# midiprog.net
KiCad netlist of a schematic drawn in EAGLE
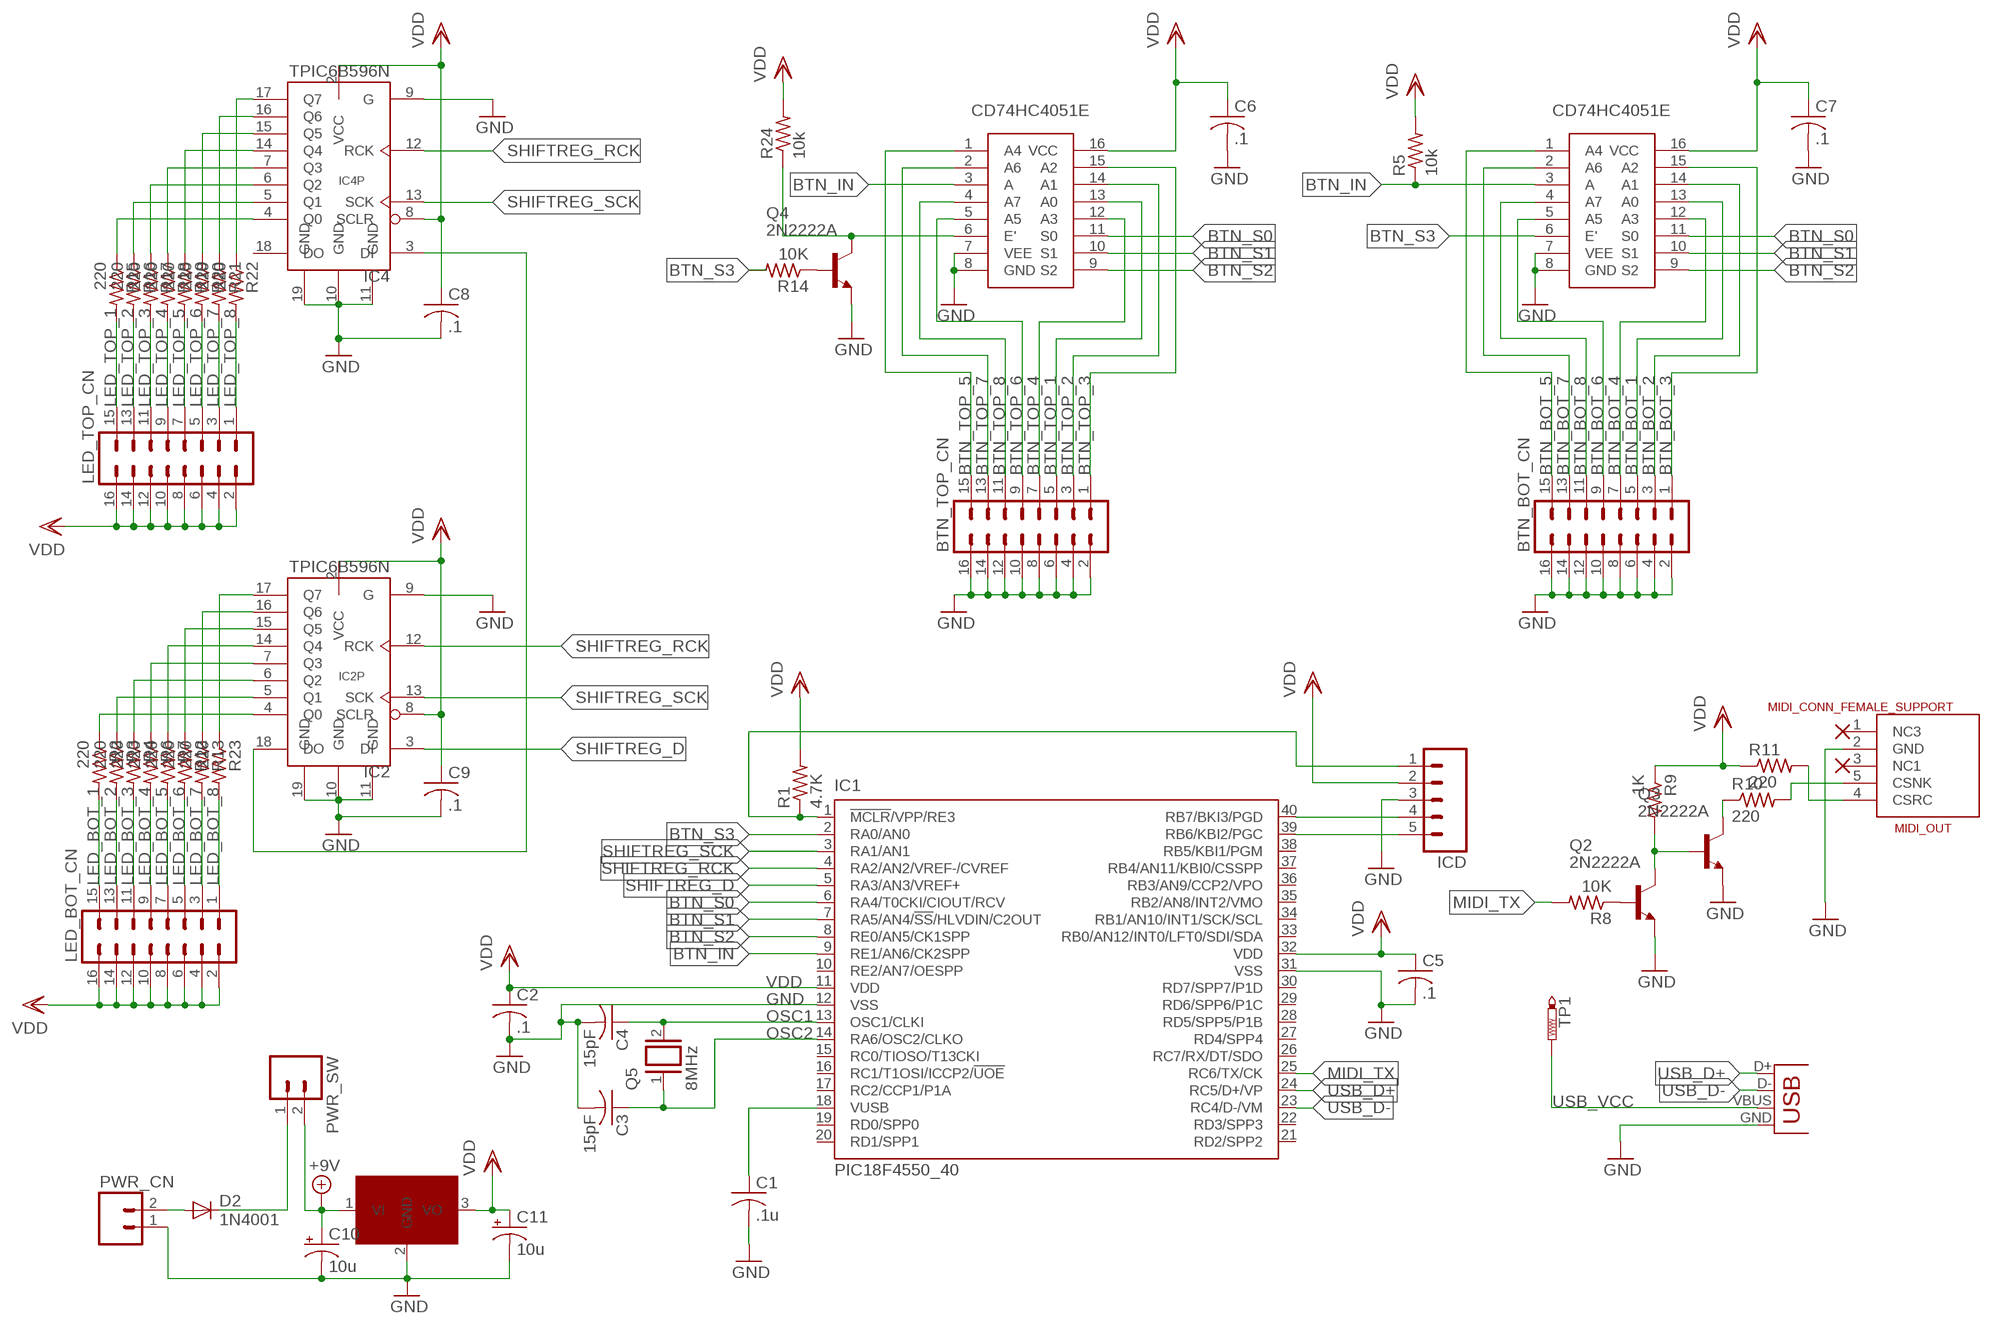
[diagram p0: schematic, sheet 1]

(export (version "E")
  (design (tool "Eeschema 10.0.6"))
  (components
    (comp (ref "BTN_BOT_CN")
      (value "MA08-2")
      (footprint "eagle-import:MA08-2")
      (libsource (lib "eagle-import") (part "MA08-2"))
    )
    (comp (ref "BTN_TOP_CN")
      (value "MA08-2")
      (footprint "eagle-import:MA08-2")
      (libsource (lib "eagle-import") (part "MA08-2"))
    )
    (comp (ref "C1")
      (value ".1u")
      (footprint "eagle-import:C050-025X075")
      (libsource (lib "eagle-import") (part "C-US050-025X075"))
    )
    (comp (ref "C2")
      (value ".1")
      (footprint "eagle-import:C050-025X075")
      (libsource (lib "eagle-import") (part "C-US050-025X075"))
    )
    (comp (ref "C3")
      (value "15pF")
      (footprint "eagle-import:C050-025X075")
      (libsource (lib "eagle-import") (part "C-US050-025X075"))
    )
    (comp (ref "C4")
      (value "15pF")
      (footprint "eagle-import:C050-025X075")
      (libsource (lib "eagle-import") (part "C-US050-025X075"))
    )
    (comp (ref "C5")
      (value ".1")
      (footprint "eagle-import:C050-025X075")
      (libsource (lib "eagle-import") (part "C-US050-025X075"))
    )
    (comp (ref "C6")
      (value ".1")
      (footprint "eagle-import:C050-025X075")
      (libsource (lib "eagle-import") (part "C-US050-025X075"))
    )
    (comp (ref "C7")
      (value ".1")
      (footprint "eagle-import:C050-025X075")
      (libsource (lib "eagle-import") (part "C-US050-025X075"))
    )
    (comp (ref "C8")
      (value ".1")
      (footprint "eagle-import:C050-025X075")
      (libsource (lib "eagle-import") (part "C-US050-025X075"))
    )
    (comp (ref "C9")
      (value ".1")
      (footprint "eagle-import:C050-025X075")
      (libsource (lib "eagle-import") (part "C-US050-025X075"))
    )
    (comp (ref "C10")
      (value "10u")
      (footprint "eagle-import:E2,5-6")
      (libsource (lib "eagle-import") (part "CPOL-USE2.5-6"))
    )
    (comp (ref "C11")
      (value "10u")
      (footprint "eagle-import:E2,5-6")
      (libsource (lib "eagle-import") (part "CPOL-USE2.5-6"))
    )
    (comp (ref "D2")
      (value "1N4001")
      (footprint "eagle-import:DO41-10")
      (libsource (lib "eagle-import") (part "1N4004"))
    )
    (comp (ref "IC1")
      (value "PIC18F4550_40")
      (footprint "eagle-import:DIL40")
      (fields (field (name "MF") "MICROCHIP") (field (name "MPN") "PIC18F4550-I/P"))
      (libsource (lib "eagle-import") (part "PIC18F4_40550"))
    )
    (comp (ref "IC2")
      (value "TPIC6B596N")
      (footprint "eagle-import:DIL20")
      (libsource (lib "eagle-import") (part "TPIC6B596N"))
    )
    (comp (ref "IC4")
      (value "TPIC6B596N")
      (footprint "eagle-import:DIL20")
      (libsource (lib "eagle-import") (part "TPIC6B596N"))
    )
    (comp (ref "ICD")
      (value "MA05")
      (footprint "eagle-import:05PA")
      (libsource (lib "eagle-import") (part "MA05"))
    )
    (comp (ref "JP1")
      (value "USB-B")
      (footprint "eagle-import:USB-B-PTH")
      (libsource (lib "eagle-import") (part "USBPTH"))
    )
    (comp (ref "LED_BOT_CN")
      (value "MA08-2")
      (footprint "eagle-import:MA08-2")
      (libsource (lib "eagle-import") (part "MA08-2"))
    )
    (comp (ref "LED_TOP_CN")
      (value "MA08-2")
      (footprint "eagle-import:MA08-2")
      (libsource (lib "eagle-import") (part "MA08-2"))
    )
    (comp (ref "MIDI_OUT")
      (value "MIDI_CONN_FEMALE_SUPPORT")
      (footprint "eagle-import:DIN_5_FEMALE_SUPPORT")
      (libsource (lib "eagle-import") (part "MIDI_CONN_FEMALE_SUPPORT"))
    )
    (comp (ref "PWR_CN")
      (value "M02")
      (footprint "eagle-import:02P")
      (libsource (lib "eagle-import") (part "M02"))
    )
    (comp (ref "PWR_SW")
      (value "M02")
      (footprint "eagle-import:02P")
      (libsource (lib "eagle-import") (part "M02"))
    )
    (comp (ref "Q2")
      (value "2N2222A")
      (footprint "eagle-import:TO18")
      (libsource (lib "eagle-import") (part "2N2222A"))
    )
    (comp (ref "Q3")
      (value "2N2222A")
      (footprint "eagle-import:TO18")
      (libsource (lib "eagle-import") (part "2N2222A"))
    )
    (comp (ref "Q4")
      (value "2N2222A")
      (footprint "eagle-import:TO18")
      (libsource (lib "eagle-import") (part "2N2222A"))
    )
    (comp (ref "Q5")
      (value "8MHz")
      (footprint "eagle-import:QS")
      (libsource (lib "eagle-import") (part "XTAL/S"))
    )
    (comp (ref "R1")
      (value "4.7K")
      (footprint "eagle-import:0207_10")
      (libsource (lib "eagle-import") (part "R-US_0207/10"))
    )
    (comp (ref "R2")
      (value "220")
      (footprint "eagle-import:0207_10")
      (libsource (lib "eagle-import") (part "R-US_0207/10"))
    )
    (comp (ref "R3")
      (value "220")
      (footprint "eagle-import:0207_10")
      (libsource (lib "eagle-import") (part "R-US_0207/10"))
    )
    (comp (ref "R4")
      (value "220")
      (footprint "eagle-import:0207_10")
      (libsource (lib "eagle-import") (part "R-US_0207/10"))
    )
    (comp (ref "R5")
      (value "10k")
      (footprint "eagle-import:0207_10")
      (libsource (lib "eagle-import") (part "R-US_0207/10"))
    )
    (comp (ref "R6")
      (value "220")
      (footprint "eagle-import:0207_10")
      (libsource (lib "eagle-import") (part "R-US_0207/10"))
    )
    (comp (ref "R7")
      (value "220")
      (footprint "eagle-import:0207_10")
      (libsource (lib "eagle-import") (part "R-US_0207/10"))
    )
    (comp (ref "R8")
      (value "10K")
      (footprint "eagle-import:0207_10")
      (libsource (lib "eagle-import") (part "R-US_0207/10"))
    )
    (comp (ref "R9")
      (value "1K")
      (footprint "eagle-import:0207_10")
      (libsource (lib "eagle-import") (part "R-US_0207/10"))
    )
    (comp (ref "R10")
      (value "220")
      (footprint "eagle-import:0207_10")
      (libsource (lib "eagle-import") (part "R-US_0207/10"))
    )
    (comp (ref "R11")
      (value "220")
      (footprint "eagle-import:0207_10")
      (libsource (lib "eagle-import") (part "R-US_0207/10"))
    )
    (comp (ref "R12")
      (value "220")
      (footprint "eagle-import:0207_10")
      (libsource (lib "eagle-import") (part "R-US_0207/10"))
    )
    (comp (ref "R13")
      (value "220")
      (footprint "eagle-import:0207_10")
      (libsource (lib "eagle-import") (part "R-US_0207/10"))
    )
    (comp (ref "R14")
      (value "10K")
      (footprint "eagle-import:0207_10")
      (libsource (lib "eagle-import") (part "R-US_0207/10"))
    )
    (comp (ref "R15")
      (value "220")
      (footprint "eagle-import:0207_10")
      (libsource (lib "eagle-import") (part "R-US_0207/10"))
    )
    (comp (ref "R16")
      (value "220")
      (footprint "eagle-import:0207_10")
      (libsource (lib "eagle-import") (part "R-US_0207/10"))
    )
    (comp (ref "R17")
      (value "220")
      (footprint "eagle-import:0207_10")
      (libsource (lib "eagle-import") (part "R-US_0207/10"))
    )
    (comp (ref "R18")
      (value "220")
      (footprint "eagle-import:0207_10")
      (libsource (lib "eagle-import") (part "R-US_0207/10"))
    )
    (comp (ref "R19")
      (value "220")
      (footprint "eagle-import:0207_10")
      (libsource (lib "eagle-import") (part "R-US_0207/10"))
    )
    (comp (ref "R20")
      (value "220")
      (footprint "eagle-import:0207_10")
      (libsource (lib "eagle-import") (part "R-US_0207/10"))
    )
    (comp (ref "R21")
      (value "220")
      (footprint "eagle-import:0207_10")
      (libsource (lib "eagle-import") (part "R-US_0207/10"))
    )
    (comp (ref "R22")
      (value "220")
      (footprint "eagle-import:0207_10")
      (libsource (lib "eagle-import") (part "R-US_0207/10"))
    )
    (comp (ref "R23")
      (value "220")
      (footprint "eagle-import:0207_10")
      (libsource (lib "eagle-import") (part "R-US_0207/10"))
    )
    (comp (ref "R24")
      (value "10k")
      (footprint "eagle-import:0207_10")
      (libsource (lib "eagle-import") (part "R-US_0207/10"))
    )
    (comp (ref "TP1")
      (value "PTR1PAD1-17")
      (footprint "eagle-import:P1-17")
      (libsource (lib "eagle-import") (part "PTR1PAD1-17"))
    )
    (comp (ref "U$1")
      (value "CD74HC4051E")
      (footprint "eagle-import:CD74HC4051E")
      (libsource (lib "eagle-import") (part "CD74HC4051E"))
    )
    (comp (ref "U$2")
      (value "CD74HC4051E")
      (footprint "eagle-import:CD74HC4051E")
      (libsource (lib "eagle-import") (part "CD74HC4051E"))
    )
    (comp (ref "U$3")
      (value "7805")
      (footprint "eagle-import:JKDFJD")
      (libsource (lib "eagle-import") (part "7805"))
    )
  )
  (nets
    (net (code "1") (name "+9V") (class "Default")
      (node (ref "C10") (pin "+") (pinfunction "+_+") (pintype "passive"))
      (node (ref "PWR_SW") (pin "2") (pinfunction "2_2") (pintype "passive"))
      (node (ref "U$3") (pin "1") (pinfunction "VI_1") (pintype "bidirectional"))
    )
    (net (code "2") (name "/BTN_BOT_1") (class "Default")
      (node (ref "BTN_BOT_CN") (pin "5") (pinfunction "5_5") (pintype "passive"))
      (node (ref "U$1") (pin "13") (pinfunction "A0_13") (pintype "bidirectional"))
    )
    (net (code "3") (name "/BTN_BOT_2") (class "Default")
      (node (ref "BTN_BOT_CN") (pin "3") (pinfunction "3_3") (pintype "passive"))
      (node (ref "U$1") (pin "14") (pinfunction "A1_14") (pintype "bidirectional"))
    )
    (net (code "4") (name "/BTN_BOT_3") (class "Default")
      (node (ref "BTN_BOT_CN") (pin "1") (pinfunction "1_1") (pintype "passive"))
      (node (ref "U$1") (pin "15") (pinfunction "A2_15") (pintype "bidirectional"))
    )
    (net (code "5") (name "/BTN_BOT_4") (class "Default")
      (node (ref "BTN_BOT_CN") (pin "7") (pinfunction "7_7") (pintype "passive"))
      (node (ref "U$1") (pin "12") (pinfunction "A3_12") (pintype "bidirectional"))
    )
    (net (code "6") (name "/BTN_BOT_5") (class "Default")
      (node (ref "BTN_BOT_CN") (pin "15") (pinfunction "15_15") (pintype "passive"))
      (node (ref "U$1") (pin "1") (pinfunction "A4_1") (pintype "bidirectional"))
    )
    (net (code "7") (name "/BTN_BOT_6") (class "Default")
      (node (ref "BTN_BOT_CN") (pin "9") (pinfunction "9_9") (pintype "passive"))
      (node (ref "U$1") (pin "5") (pinfunction "A5_5") (pintype "bidirectional"))
    )
    (net (code "8") (name "/BTN_BOT_7") (class "Default")
      (node (ref "BTN_BOT_CN") (pin "13") (pinfunction "13_13") (pintype "passive"))
      (node (ref "U$1") (pin "2") (pinfunction "A6_2") (pintype "bidirectional"))
    )
    (net (code "9") (name "/BTN_BOT_8") (class "Default")
      (node (ref "BTN_BOT_CN") (pin "11") (pinfunction "11_11") (pintype "passive"))
      (node (ref "U$1") (pin "4") (pinfunction "A7_4") (pintype "bidirectional"))
    )
    (net (code "10") (name "/BTN_TOP_1") (class "Default")
      (node (ref "BTN_TOP_CN") (pin "5") (pinfunction "5_5") (pintype "passive"))
      (node (ref "U$2") (pin "13") (pinfunction "A0_13") (pintype "bidirectional"))
    )
    (net (code "11") (name "/BTN_TOP_2") (class "Default")
      (node (ref "BTN_TOP_CN") (pin "3") (pinfunction "3_3") (pintype "passive"))
      (node (ref "U$2") (pin "14") (pinfunction "A1_14") (pintype "bidirectional"))
    )
    (net (code "12") (name "/BTN_TOP_3") (class "Default")
      (node (ref "BTN_TOP_CN") (pin "1") (pinfunction "1_1") (pintype "passive"))
      (node (ref "U$2") (pin "15") (pinfunction "A2_15") (pintype "bidirectional"))
    )
    (net (code "13") (name "/BTN_TOP_4") (class "Default")
      (node (ref "BTN_TOP_CN") (pin "7") (pinfunction "7_7") (pintype "passive"))
      (node (ref "U$2") (pin "12") (pinfunction "A3_12") (pintype "bidirectional"))
    )
    (net (code "14") (name "/BTN_TOP_5") (class "Default")
      (node (ref "BTN_TOP_CN") (pin "15") (pinfunction "15_15") (pintype "passive"))
      (node (ref "U$2") (pin "1") (pinfunction "A4_1") (pintype "bidirectional"))
    )
    (net (code "15") (name "/BTN_TOP_6") (class "Default")
      (node (ref "BTN_TOP_CN") (pin "9") (pinfunction "9_9") (pintype "passive"))
      (node (ref "U$2") (pin "5") (pinfunction "A5_5") (pintype "bidirectional"))
    )
    (net (code "16") (name "/BTN_TOP_7") (class "Default")
      (node (ref "BTN_TOP_CN") (pin "13") (pinfunction "13_13") (pintype "passive"))
      (node (ref "U$2") (pin "2") (pinfunction "A6_2") (pintype "bidirectional"))
    )
    (net (code "17") (name "/BTN_TOP_8") (class "Default")
      (node (ref "BTN_TOP_CN") (pin "11") (pinfunction "11_11") (pintype "passive"))
      (node (ref "U$2") (pin "4") (pinfunction "A7_4") (pintype "bidirectional"))
    )
    (net (code "18") (name "/LED_BOT_1") (class "Default")
      (node (ref "LED_BOT_CN") (pin "15") (pinfunction "15_15") (pintype "passive"))
      (node (ref "R2") (pin "2") (pinfunction "2_2") (pintype "passive"))
    )
    (net (code "19") (name "/LED_BOT_2") (class "Default")
      (node (ref "LED_BOT_CN") (pin "13") (pinfunction "13_13") (pintype "passive"))
      (node (ref "R3") (pin "2") (pinfunction "2_2") (pintype "passive"))
    )
    (net (code "20") (name "/LED_BOT_3") (class "Default")
      (node (ref "LED_BOT_CN") (pin "11") (pinfunction "11_11") (pintype "passive"))
      (node (ref "R4") (pin "2") (pinfunction "2_2") (pintype "passive"))
    )
    (net (code "21") (name "/LED_BOT_4") (class "Default")
      (node (ref "LED_BOT_CN") (pin "9") (pinfunction "9_9") (pintype "passive"))
      (node (ref "R6") (pin "2") (pinfunction "2_2") (pintype "passive"))
    )
    (net (code "22") (name "/LED_BOT_5") (class "Default")
      (node (ref "LED_BOT_CN") (pin "7") (pinfunction "7_7") (pintype "passive"))
      (node (ref "R7") (pin "2") (pinfunction "2_2") (pintype "passive"))
    )
    (net (code "23") (name "/LED_BOT_6") (class "Default")
      (node (ref "LED_BOT_CN") (pin "5") (pinfunction "5_5") (pintype "passive"))
      (node (ref "R12") (pin "2") (pinfunction "2_2") (pintype "passive"))
    )
    (net (code "24") (name "/LED_BOT_7") (class "Default")
      (node (ref "LED_BOT_CN") (pin "3") (pinfunction "3_3") (pintype "passive"))
      (node (ref "R13") (pin "2") (pinfunction "2_2") (pintype "passive"))
    )
    (net (code "25") (name "/LED_BOT_8") (class "Default")
      (node (ref "LED_BOT_CN") (pin "1") (pinfunction "1_1") (pintype "passive"))
      (node (ref "R23") (pin "2") (pinfunction "2_2") (pintype "passive"))
    )
    (net (code "26") (name "/LED_TOP_1") (class "Default")
      (node (ref "LED_TOP_CN") (pin "15") (pinfunction "15_15") (pintype "passive"))
      (node (ref "R15") (pin "2") (pinfunction "2_2") (pintype "passive"))
    )
    (net (code "27") (name "/LED_TOP_2") (class "Default")
      (node (ref "LED_TOP_CN") (pin "13") (pinfunction "13_13") (pintype "passive"))
      (node (ref "R16") (pin "2") (pinfunction "2_2") (pintype "passive"))
    )
    (net (code "28") (name "/LED_TOP_3") (class "Default")
      (node (ref "LED_TOP_CN") (pin "11") (pinfunction "11_11") (pintype "passive"))
      (node (ref "R17") (pin "2") (pinfunction "2_2") (pintype "passive"))
    )
    (net (code "29") (name "/LED_TOP_4") (class "Default")
      (node (ref "LED_TOP_CN") (pin "9") (pinfunction "9_9") (pintype "passive"))
      (node (ref "R18") (pin "2") (pinfunction "2_2") (pintype "passive"))
    )
    (net (code "30") (name "/LED_TOP_5") (class "Default")
      (node (ref "LED_TOP_CN") (pin "7") (pinfunction "7_7") (pintype "passive"))
      (node (ref "R19") (pin "2") (pinfunction "2_2") (pintype "passive"))
    )
    (net (code "31") (name "/LED_TOP_6") (class "Default")
      (node (ref "LED_TOP_CN") (pin "5") (pinfunction "5_5") (pintype "passive"))
      (node (ref "R20") (pin "2") (pinfunction "2_2") (pintype "passive"))
    )
    (net (code "32") (name "/LED_TOP_7") (class "Default")
      (node (ref "LED_TOP_CN") (pin "3") (pinfunction "3_3") (pintype "passive"))
      (node (ref "R21") (pin "2") (pinfunction "2_2") (pintype "passive"))
    )
    (net (code "33") (name "/LED_TOP_8") (class "Default")
      (node (ref "LED_TOP_CN") (pin "1") (pinfunction "1_1") (pintype "passive"))
      (node (ref "R22") (pin "2") (pinfunction "2_2") (pintype "passive"))
    )
    (net (code "34") (name "/OSC1") (class "Default")
      (node (ref "C4") (pin "1") (pinfunction "1_1") (pintype "passive"))
      (node (ref "IC1") (pin "13") (pinfunction "OSC1/CLKI_13") (pintype "input"))
      (node (ref "Q5") (pin "2") (pinfunction "2_2") (pintype "passive"))
    )
    (net (code "35") (name "/OSC2") (class "Default")
      (node (ref "C3") (pin "1") (pinfunction "1_1") (pintype "passive"))
      (node (ref "IC1") (pin "14") (pinfunction "RA6/OSC2/CLKO_14") (pintype "output"))
      (node (ref "Q5") (pin "1") (pinfunction "1_1") (pintype "passive"))
    )
    (net (code "36") (name "/USB_VCC") (class "Default")
      (node (ref "JP1") (pin "VBUS") (pinfunction "VBUS_VBUS") (pintype "bidirectional"))
      (node (ref "TP1") (pin "TP") (pinfunction "TP_TP") (pintype "input"))
    )
    (net (code "37") (name "BTN_IN") (class "Default")
      (node (ref "IC1") (pin "9") (pinfunction "RE1/AN6/CK2SPP_9") (pintype "bidirectional"))
      (node (ref "R5") (pin "1") (pinfunction "1_1") (pintype "passive"))
      (node (ref "U$1") (pin "3") (pinfunction "A_3") (pintype "bidirectional"))
      (node (ref "U$2") (pin "3") (pinfunction "A_3") (pintype "bidirectional"))
    )
    (net (code "38") (name "BTN_S0") (class "Default")
      (node (ref "IC1") (pin "6") (pinfunction "RA4/T0CKI/CIOUT/RCV_6") (pintype "bidirectional"))
      (node (ref "U$1") (pin "11") (pinfunction "S0_11") (pintype "bidirectional"))
      (node (ref "U$2") (pin "11") (pinfunction "S0_11") (pintype "bidirectional"))
    )
    (net (code "39") (name "BTN_S1") (class "Default")
      (node (ref "IC1") (pin "7") (pinfunction "RA5/AN4/~{SS}/HLVDIN/C2OUT_7") (pintype "bidirectional"))
      (node (ref "U$1") (pin "10") (pinfunction "S1_10") (pintype "bidirectional"))
      (node (ref "U$2") (pin "10") (pinfunction "S1_10") (pintype "bidirectional"))
    )
    (net (code "40") (name "BTN_S2") (class "Default")
      (node (ref "IC1") (pin "8") (pinfunction "RE0/AN5/CK1SPP_8") (pintype "bidirectional"))
      (node (ref "U$1") (pin "9") (pinfunction "S2_9") (pintype "bidirectional"))
      (node (ref "U$2") (pin "9") (pinfunction "S2_9") (pintype "bidirectional"))
    )
    (net (code "41") (name "BTN_S3") (class "Default")
      (node (ref "IC1") (pin "2") (pinfunction "RA0/AN0_2") (pintype "bidirectional"))
      (node (ref "R14") (pin "2") (pinfunction "2_2") (pintype "passive"))
      (node (ref "U$1") (pin "6") (pinfunction "E'_6") (pintype "bidirectional"))
    )
    (net (code "42") (name "GND") (class "Default")
      (node (ref "BTN_BOT_CN") (pin "10") (pinfunction "10_10") (pintype "passive"))
      (node (ref "BTN_BOT_CN") (pin "12") (pinfunction "12_12") (pintype "passive"))
      (node (ref "BTN_BOT_CN") (pin "14") (pinfunction "14_14") (pintype "passive"))
      (node (ref "BTN_BOT_CN") (pin "16") (pinfunction "16_16") (pintype "passive"))
      (node (ref "BTN_BOT_CN") (pin "2") (pinfunction "2_2") (pintype "passive"))
      (node (ref "BTN_BOT_CN") (pin "4") (pinfunction "4_4") (pintype "passive"))
      (node (ref "BTN_BOT_CN") (pin "6") (pinfunction "6_6") (pintype "passive"))
      (node (ref "BTN_BOT_CN") (pin "8") (pinfunction "8_8") (pintype "passive"))
      (node (ref "BTN_TOP_CN") (pin "10") (pinfunction "10_10") (pintype "passive"))
      (node (ref "BTN_TOP_CN") (pin "12") (pinfunction "12_12") (pintype "passive"))
      (node (ref "BTN_TOP_CN") (pin "14") (pinfunction "14_14") (pintype "passive"))
      (node (ref "BTN_TOP_CN") (pin "16") (pinfunction "16_16") (pintype "passive"))
      (node (ref "BTN_TOP_CN") (pin "2") (pinfunction "2_2") (pintype "passive"))
      (node (ref "BTN_TOP_CN") (pin "4") (pinfunction "4_4") (pintype "passive"))
      (node (ref "BTN_TOP_CN") (pin "6") (pinfunction "6_6") (pintype "passive"))
      (node (ref "BTN_TOP_CN") (pin "8") (pinfunction "8_8") (pintype "passive"))
      (node (ref "C1") (pin "2") (pinfunction "2_2") (pintype "passive"))
      (node (ref "C10") (pin "-") (pinfunction "-_-") (pintype "passive"))
      (node (ref "C11") (pin "-") (pinfunction "-_-") (pintype "passive"))
      (node (ref "C2") (pin "2") (pinfunction "2_2") (pintype "passive"))
      (node (ref "C3") (pin "2") (pinfunction "2_2") (pintype "passive"))
      (node (ref "C4") (pin "2") (pinfunction "2_2") (pintype "passive"))
      (node (ref "C5") (pin "2") (pinfunction "2_2") (pintype "passive"))
      (node (ref "C6") (pin "2") (pinfunction "2_2") (pintype "passive"))
      (node (ref "C7") (pin "2") (pinfunction "2_2") (pintype "passive"))
      (node (ref "C8") (pin "2") (pinfunction "2_2") (pintype "passive"))
      (node (ref "C9") (pin "2") (pinfunction "2_2") (pintype "passive"))
      (node (ref "IC1") (pin "12") (pinfunction "VSS_12") (pintype "power_in"))
      (node (ref "IC1") (pin "31") (pinfunction "VSS_31") (pintype "power_in"))
      (node (ref "IC2") (pin "10") (pinfunction "GND_10") (pintype "power_in"))
      (node (ref "IC2") (pin "11") (pinfunction "GND_11") (pintype "power_in"))
      (node (ref "IC2") (pin "19") (pinfunction "GND_19") (pintype "power_in"))
      (node (ref "IC2") (pin "9") (pinfunction "G_9") (pintype "input"))
      (node (ref "IC4") (pin "10") (pinfunction "GND_10") (pintype "power_in"))
      (node (ref "IC4") (pin "11") (pinfunction "GND_11") (pintype "power_in"))
      (node (ref "IC4") (pin "19") (pinfunction "GND_19") (pintype "power_in"))
      (node (ref "IC4") (pin "9") (pinfunction "G_9") (pintype "input"))
      (node (ref "ICD") (pin "3") (pinfunction "3_3") (pintype "passive"))
      (node (ref "JP1") (pin "GND") (pinfunction "GND_GND") (pintype "bidirectional"))
      (node (ref "MIDI_OUT") (pin "2") (pinfunction "GND_2") (pintype "bidirectional"))
      (node (ref "PWR_CN") (pin "1") (pinfunction "1_1") (pintype "passive"))
      (node (ref "Q2") (pin "1") (pinfunction "E_1") (pintype "passive"))
      (node (ref "Q3") (pin "1") (pinfunction "E_1") (pintype "passive"))
      (node (ref "Q4") (pin "1") (pinfunction "E_1") (pintype "passive"))
      (node (ref "U$1") (pin "7") (pinfunction "VEE_7") (pintype "bidirectional"))
      (node (ref "U$1") (pin "8") (pinfunction "GND_8") (pintype "bidirectional"))
      (node (ref "U$2") (pin "7") (pinfunction "VEE_7") (pintype "bidirectional"))
      (node (ref "U$2") (pin "8") (pinfunction "GND_8") (pintype "bidirectional"))
      (node (ref "U$3") (pin "2") (pinfunction "GND_2") (pintype "bidirectional"))
    )
    (net (code "43") (name "MIDI_TX") (class "Default")
      (node (ref "IC1") (pin "25") (pinfunction "RC6/TX/CK_25") (pintype "bidirectional"))
      (node (ref "R8") (pin "2") (pinfunction "2_2") (pintype "passive"))
    )
    (net (code "44") (name "Net-(D2-PadA)") (class "Default")
      (node (ref "D2") (pin "A") (pinfunction "A_A") (pintype "passive"))
      (node (ref "PWR_CN") (pin "2") (pinfunction "2_2") (pintype "passive"))
    )
    (net (code "45") (name "Net-(D2-PadC)") (class "Default")
      (node (ref "D2") (pin "C") (pinfunction "C_C") (pintype "passive"))
      (node (ref "PWR_SW") (pin "1") (pinfunction "1_1") (pintype "passive"))
    )
    (net (code "46") (name "Net-(IC1-RB6{slash}KBI2{slash}PGC)") (class "Default")
      (node (ref "IC1") (pin "39") (pinfunction "RB6/KBI2/PGC_39") (pintype "bidirectional"))
      (node (ref "ICD") (pin "5") (pinfunction "5_5") (pintype "passive"))
    )
    (net (code "47") (name "Net-(IC1-RB7{slash}BKI3{slash}PGD)") (class "Default")
      (node (ref "IC1") (pin "40") (pinfunction "RB7/BKI3/PGD_40") (pintype "bidirectional"))
      (node (ref "ICD") (pin "4") (pinfunction "4_4") (pintype "passive"))
    )
    (net (code "48") (name "Net-(IC1-VUSB)") (class "Default")
      (node (ref "C1") (pin "1") (pinfunction "1_1") (pintype "passive"))
      (node (ref "IC1") (pin "18") (pinfunction "VUSB_18") (pintype "bidirectional"))
    )
    (net (code "49") (name "Net-(IC1-~{MCLR}{slash}VPP{slash}RE3)") (class "Default")
      (node (ref "IC1") (pin "1") (pinfunction "~{MCLR}/VPP/RE3_1") (pintype "input"))
      (node (ref "ICD") (pin "1") (pinfunction "1_1") (pintype "passive"))
      (node (ref "R1") (pin "1") (pinfunction "1_1") (pintype "passive"))
    )
    (net (code "50") (name "Net-(IC2A-DO)") (class "Default")
      (node (ref "IC2") (pin "18") (pinfunction "DO_18") (pintype "output"))
      (node (ref "IC4") (pin "3") (pinfunction "DI_3") (pintype "input"))
    )
    (net (code "51") (name "Net-(IC2A-Q0)") (class "Default")
      (node (ref "IC2") (pin "4") (pinfunction "Q0_4") (pintype "open_collector"))
      (node (ref "R2") (pin "1") (pinfunction "1_1") (pintype "passive"))
    )
    (net (code "52") (name "Net-(IC2A-Q1)") (class "Default")
      (node (ref "IC2") (pin "5") (pinfunction "Q1_5") (pintype "open_collector"))
      (node (ref "R3") (pin "1") (pinfunction "1_1") (pintype "passive"))
    )
    (net (code "53") (name "Net-(IC2A-Q2)") (class "Default")
      (node (ref "IC2") (pin "6") (pinfunction "Q2_6") (pintype "open_collector"))
      (node (ref "R4") (pin "1") (pinfunction "1_1") (pintype "passive"))
    )
    (net (code "54") (name "Net-(IC2A-Q3)") (class "Default")
      (node (ref "IC2") (pin "7") (pinfunction "Q3_7") (pintype "open_collector"))
      (node (ref "R6") (pin "1") (pinfunction "1_1") (pintype "passive"))
    )
    (net (code "55") (name "Net-(IC2A-Q4)") (class "Default")
      (node (ref "IC2") (pin "14") (pinfunction "Q4_14") (pintype "open_collector"))
      (node (ref "R7") (pin "1") (pinfunction "1_1") (pintype "passive"))
    )
    (net (code "56") (name "Net-(IC2A-Q5)") (class "Default")
      (node (ref "IC2") (pin "15") (pinfunction "Q5_15") (pintype "open_collector"))
      (node (ref "R12") (pin "1") (pinfunction "1_1") (pintype "passive"))
    )
    (net (code "57") (name "Net-(IC2A-Q6)") (class "Default")
      (node (ref "IC2") (pin "16") (pinfunction "Q6_16") (pintype "open_collector"))
      (node (ref "R13") (pin "1") (pinfunction "1_1") (pintype "passive"))
    )
    (net (code "58") (name "Net-(IC2A-Q7)") (class "Default")
      (node (ref "IC2") (pin "17") (pinfunction "Q7_17") (pintype "open_collector"))
      (node (ref "R23") (pin "1") (pinfunction "1_1") (pintype "passive"))
    )
    (net (code "59") (name "Net-(IC4A-Q0)") (class "Default")
      (node (ref "IC4") (pin "4") (pinfunction "Q0_4") (pintype "open_collector"))
      (node (ref "R15") (pin "1") (pinfunction "1_1") (pintype "passive"))
    )
    (net (code "60") (name "Net-(IC4A-Q1)") (class "Default")
      (node (ref "IC4") (pin "5") (pinfunction "Q1_5") (pintype "open_collector"))
      (node (ref "R16") (pin "1") (pinfunction "1_1") (pintype "passive"))
    )
    (net (code "61") (name "Net-(IC4A-Q2)") (class "Default")
      (node (ref "IC4") (pin "6") (pinfunction "Q2_6") (pintype "open_collector"))
      (node (ref "R17") (pin "1") (pinfunction "1_1") (pintype "passive"))
    )
    (net (code "62") (name "Net-(IC4A-Q3)") (class "Default")
      (node (ref "IC4") (pin "7") (pinfunction "Q3_7") (pintype "open_collector"))
      (node (ref "R18") (pin "1") (pinfunction "1_1") (pintype "passive"))
    )
    (net (code "63") (name "Net-(IC4A-Q4)") (class "Default")
      (node (ref "IC4") (pin "14") (pinfunction "Q4_14") (pintype "open_collector"))
      (node (ref "R19") (pin "1") (pinfunction "1_1") (pintype "passive"))
    )
    (net (code "64") (name "Net-(IC4A-Q5)") (class "Default")
      (node (ref "IC4") (pin "15") (pinfunction "Q5_15") (pintype "open_collector"))
      (node (ref "R20") (pin "1") (pinfunction "1_1") (pintype "passive"))
    )
    (net (code "65") (name "Net-(IC4A-Q6)") (class "Default")
      (node (ref "IC4") (pin "16") (pinfunction "Q6_16") (pintype "open_collector"))
      (node (ref "R21") (pin "1") (pinfunction "1_1") (pintype "passive"))
    )
    (net (code "66") (name "Net-(IC4A-Q7)") (class "Default")
      (node (ref "IC4") (pin "17") (pinfunction "Q7_17") (pintype "open_collector"))
      (node (ref "R22") (pin "1") (pinfunction "1_1") (pintype "passive"))
    )
    (net (code "67") (name "Net-(MIDI_OUT-CSNK)") (class "Default")
      (node (ref "MIDI_OUT") (pin "5") (pinfunction "CSNK_5") (pintype "bidirectional"))
      (node (ref "R10") (pin "2") (pinfunction "2_2") (pintype "passive"))
    )
    (net (code "68") (name "Net-(MIDI_OUT-CSRC)") (class "Default")
      (node (ref "MIDI_OUT") (pin "4") (pinfunction "CSRC_4") (pintype "bidirectional"))
      (node (ref "R11") (pin "2") (pinfunction "2_2") (pintype "passive"))
    )
    (net (code "69") (name "Net-(Q2-B)") (class "Default")
      (node (ref "Q2") (pin "2") (pinfunction "B_2") (pintype "passive"))
      (node (ref "R8") (pin "1") (pinfunction "1_1") (pintype "passive"))
    )
    (net (code "70") (name "Net-(Q2-C)") (class "Default")
      (node (ref "Q2") (pin "3") (pinfunction "C_3") (pintype "passive"))
      (node (ref "Q3") (pin "2") (pinfunction "B_2") (pintype "passive"))
      (node (ref "R9") (pin "2") (pinfunction "2_2") (pintype "passive"))
    )
    (net (code "71") (name "Net-(Q3-C)") (class "Default")
      (node (ref "Q3") (pin "3") (pinfunction "C_3") (pintype "passive"))
      (node (ref "R10") (pin "1") (pinfunction "1_1") (pintype "passive"))
    )
    (net (code "72") (name "Net-(Q4-B)") (class "Default")
      (node (ref "Q4") (pin "2") (pinfunction "B_2") (pintype "passive"))
      (node (ref "R14") (pin "1") (pinfunction "1_1") (pintype "passive"))
    )
    (net (code "73") (name "Net-(Q4-C)") (class "Default")
      (node (ref "Q4") (pin "3") (pinfunction "C_3") (pintype "passive"))
      (node (ref "R24") (pin "1") (pinfunction "1_1") (pintype "passive"))
      (node (ref "U$2") (pin "6") (pinfunction "E'_6") (pintype "bidirectional"))
    )
    (net (code "74") (name "SHIFTREG_D") (class "Default")
      (node (ref "IC1") (pin "5") (pinfunction "RA3/AN3/VREF+_5") (pintype "bidirectional"))
      (node (ref "IC2") (pin "3") (pinfunction "DI_3") (pintype "input"))
    )
    (net (code "75") (name "SHIFTREG_RCK") (class "Default")
      (node (ref "IC1") (pin "4") (pinfunction "RA2/AN2/VREF-/CVREF_4") (pintype "bidirectional"))
      (node (ref "IC2") (pin "12") (pinfunction "RCK_12") (pintype "input"))
      (node (ref "IC4") (pin "12") (pinfunction "RCK_12") (pintype "input"))
    )
    (net (code "76") (name "SHIFTREG_SCK") (class "Default")
      (node (ref "IC1") (pin "3") (pinfunction "RA1/AN1_3") (pintype "bidirectional"))
      (node (ref "IC2") (pin "13") (pinfunction "SCK_13") (pintype "input"))
      (node (ref "IC4") (pin "13") (pinfunction "SCK_13") (pintype "input"))
    )
    (net (code "77") (name "USB_D+") (class "Default")
      (node (ref "IC1") (pin "24") (pinfunction "RC5/D+/VP_24") (pintype "bidirectional"))
      (node (ref "JP1") (pin "D+") (pinfunction "D+_D+") (pintype "bidirectional"))
    )
    (net (code "78") (name "USB_D-") (class "Default")
      (node (ref "IC1") (pin "23") (pinfunction "RC4/D-/VM_23") (pintype "bidirectional"))
      (node (ref "JP1") (pin "D-") (pinfunction "D-_D-") (pintype "bidirectional"))
    )
    (net (code "79") (name "VDD") (class "Default")
      (node (ref "C11") (pin "+") (pinfunction "+_+") (pintype "passive"))
      (node (ref "C2") (pin "1") (pinfunction "1_1") (pintype "passive"))
      (node (ref "C5") (pin "1") (pinfunction "1_1") (pintype "passive"))
      (node (ref "C6") (pin "1") (pinfunction "1_1") (pintype "passive"))
      (node (ref "C7") (pin "1") (pinfunction "1_1") (pintype "passive"))
      (node (ref "C8") (pin "1") (pinfunction "1_1") (pintype "passive"))
      (node (ref "C9") (pin "1") (pinfunction "1_1") (pintype "passive"))
      (node (ref "IC1") (pin "11") (pinfunction "VDD_11") (pintype "power_in"))
      (node (ref "IC1") (pin "32") (pinfunction "VDD_32") (pintype "power_in"))
      (node (ref "IC2") (pin "2") (pinfunction "VCC_2") (pintype "power_in"))
      (node (ref "IC2") (pin "8") (pinfunction "SCLR_8") (pintype "input"))
      (node (ref "IC4") (pin "2") (pinfunction "VCC_2") (pintype "power_in"))
      (node (ref "IC4") (pin "8") (pinfunction "SCLR_8") (pintype "input"))
      (node (ref "ICD") (pin "2") (pinfunction "2_2") (pintype "passive"))
      (node (ref "LED_BOT_CN") (pin "10") (pinfunction "10_10") (pintype "passive"))
      (node (ref "LED_BOT_CN") (pin "12") (pinfunction "12_12") (pintype "passive"))
      (node (ref "LED_BOT_CN") (pin "14") (pinfunction "14_14") (pintype "passive"))
      (node (ref "LED_BOT_CN") (pin "16") (pinfunction "16_16") (pintype "passive"))
      (node (ref "LED_BOT_CN") (pin "2") (pinfunction "2_2") (pintype "passive"))
      (node (ref "LED_BOT_CN") (pin "4") (pinfunction "4_4") (pintype "passive"))
      (node (ref "LED_BOT_CN") (pin "6") (pinfunction "6_6") (pintype "passive"))
      (node (ref "LED_BOT_CN") (pin "8") (pinfunction "8_8") (pintype "passive"))
      (node (ref "LED_TOP_CN") (pin "10") (pinfunction "10_10") (pintype "passive"))
      (node (ref "LED_TOP_CN") (pin "12") (pinfunction "12_12") (pintype "passive"))
      (node (ref "LED_TOP_CN") (pin "14") (pinfunction "14_14") (pintype "passive"))
      (node (ref "LED_TOP_CN") (pin "16") (pinfunction "16_16") (pintype "passive"))
      (node (ref "LED_TOP_CN") (pin "2") (pinfunction "2_2") (pintype "passive"))
      (node (ref "LED_TOP_CN") (pin "4") (pinfunction "4_4") (pintype "passive"))
      (node (ref "LED_TOP_CN") (pin "6") (pinfunction "6_6") (pintype "passive"))
      (node (ref "LED_TOP_CN") (pin "8") (pinfunction "8_8") (pintype "passive"))
      (node (ref "R1") (pin "2") (pinfunction "2_2") (pintype "passive"))
      (node (ref "R11") (pin "1") (pinfunction "1_1") (pintype "passive"))
      (node (ref "R24") (pin "2") (pinfunction "2_2") (pintype "passive"))
      (node (ref "R5") (pin "2") (pinfunction "2_2") (pintype "passive"))
      (node (ref "R9") (pin "1") (pinfunction "1_1") (pintype "passive"))
      (node (ref "U$1") (pin "16") (pinfunction "VCC_16") (pintype "bidirectional"))
      (node (ref "U$2") (pin "16") (pinfunction "VCC_16") (pintype "bidirectional"))
      (node (ref "U$3") (pin "3") (pinfunction "VO_3") (pintype "bidirectional"))
    )
    (net (code "80") (name "unconnected-(IC1-RB0{slash}AN12{slash}INT0{slash}LFT0{slash}SDI{slash}SDA-Pad33)") (class "Default")
      (node (ref "IC1") (pin "33") (pinfunction "RB0/AN12/INT0/LFT0/SDI/SDA_33") (pintype "bidirectional"))
    )
    (net (code "81") (name "unconnected-(IC1-RB1{slash}AN10{slash}INT1{slash}SCK{slash}SCL-Pad34)") (class "Default")
      (node (ref "IC1") (pin "34") (pinfunction "RB1/AN10/INT1/SCK/SCL_34") (pintype "bidirectional"))
    )
    (net (code "82") (name "unconnected-(IC1-RB2{slash}AN8{slash}INT2{slash}VMO-Pad35)") (class "Default")
      (node (ref "IC1") (pin "35") (pinfunction "RB2/AN8/INT2/VMO_35") (pintype "bidirectional"))
    )
    (net (code "83") (name "unconnected-(IC1-RB3{slash}AN9{slash}CCP2{slash}VPO-Pad36)") (class "Default")
      (node (ref "IC1") (pin "36") (pinfunction "RB3/AN9/CCP2/VPO_36") (pintype "bidirectional"))
    )
    (net (code "84") (name "unconnected-(IC1-RB4{slash}AN11{slash}KBI0{slash}CSSPP-Pad37)") (class "Default")
      (node (ref "IC1") (pin "37") (pinfunction "RB4/AN11/KBI0/CSSPP_37") (pintype "bidirectional"))
    )
    (net (code "85") (name "unconnected-(IC1-RB5{slash}KBI1{slash}PGM-Pad38)") (class "Default")
      (node (ref "IC1") (pin "38") (pinfunction "RB5/KBI1/PGM_38") (pintype "bidirectional"))
    )
    (net (code "86") (name "unconnected-(IC1-RC0{slash}TIOSO{slash}T13CKI-Pad15)") (class "Default")
      (node (ref "IC1") (pin "15") (pinfunction "RC0/TIOSO/T13CKI_15") (pintype "bidirectional"))
    )
    (net (code "87") (name "unconnected-(IC1-RC1{slash}T1OSI{slash}ICCP2{slash}~{UOE}-Pad16)") (class "Default")
      (node (ref "IC1") (pin "16") (pinfunction "RC1/T1OSI/ICCP2/~{UOE}_16") (pintype "bidirectional"))
    )
    (net (code "88") (name "unconnected-(IC1-RC2{slash}CCP1{slash}P1A-Pad17)") (class "Default")
      (node (ref "IC1") (pin "17") (pinfunction "RC2/CCP1/P1A_17") (pintype "bidirectional"))
    )
    (net (code "89") (name "unconnected-(IC1-RC7{slash}RX{slash}DT{slash}SDO-Pad26)") (class "Default")
      (node (ref "IC1") (pin "26") (pinfunction "RC7/RX/DT/SDO_26") (pintype "bidirectional"))
    )
    (net (code "90") (name "unconnected-(IC1-RD0{slash}SPP0-Pad19)") (class "Default")
      (node (ref "IC1") (pin "19") (pinfunction "RD0/SPP0_19") (pintype "bidirectional"))
    )
    (net (code "91") (name "unconnected-(IC1-RD1{slash}SPP1-Pad20)") (class "Default")
      (node (ref "IC1") (pin "20") (pinfunction "RD1/SPP1_20") (pintype "bidirectional"))
    )
    (net (code "92") (name "unconnected-(IC1-RD2{slash}SPP2-Pad21)") (class "Default")
      (node (ref "IC1") (pin "21") (pinfunction "RD2/SPP2_21") (pintype "bidirectional"))
    )
    (net (code "93") (name "unconnected-(IC1-RD3{slash}SPP3-Pad22)") (class "Default")
      (node (ref "IC1") (pin "22") (pinfunction "RD3/SPP3_22") (pintype "bidirectional"))
    )
    (net (code "94") (name "unconnected-(IC1-RD4{slash}SPP4-Pad27)") (class "Default")
      (node (ref "IC1") (pin "27") (pinfunction "RD4/SPP4_27") (pintype "bidirectional"))
    )
    (net (code "95") (name "unconnected-(IC1-RD5{slash}SPP5{slash}P1B-Pad28)") (class "Default")
      (node (ref "IC1") (pin "28") (pinfunction "RD5/SPP5/P1B_28") (pintype "bidirectional"))
    )
    (net (code "96") (name "unconnected-(IC1-RD6{slash}SPP6{slash}P1C-Pad29)") (class "Default")
      (node (ref "IC1") (pin "29") (pinfunction "RD6/SPP6/P1C_29") (pintype "bidirectional"))
    )
    (net (code "97") (name "unconnected-(IC1-RD7{slash}SPP7{slash}P1D-Pad30)") (class "Default")
      (node (ref "IC1") (pin "30") (pinfunction "RD7/SPP7/P1D_30") (pintype "bidirectional"))
    )
    (net (code "98") (name "unconnected-(IC1-RE2{slash}AN7{slash}OESPP-Pad10)") (class "Default")
      (node (ref "IC1") (pin "10") (pinfunction "RE2/AN7/OESPP_10") (pintype "bidirectional"))
    )
    (net (code "99") (name "unconnected-(IC4A-DO-Pad18)") (class "Default")
      (node (ref "IC4") (pin "18") (pinfunction "DO_18") (pintype "output"))
    )
    (net (code "100") (name "unconnected-(MIDI_OUT-NC1-Pad3)") (class "Default")
      (node (ref "MIDI_OUT") (pin "3") (pinfunction "NC1_3") (pintype "bidirectional"))
    )
    (net (code "101") (name "unconnected-(MIDI_OUT-NC3-Pad1)") (class "Default")
      (node (ref "MIDI_OUT") (pin "1") (pinfunction "NC3_1") (pintype "bidirectional"))
    )
  )
)
